# Interface2.net
KiCad netlist of a schematic drawn in Altium Designer
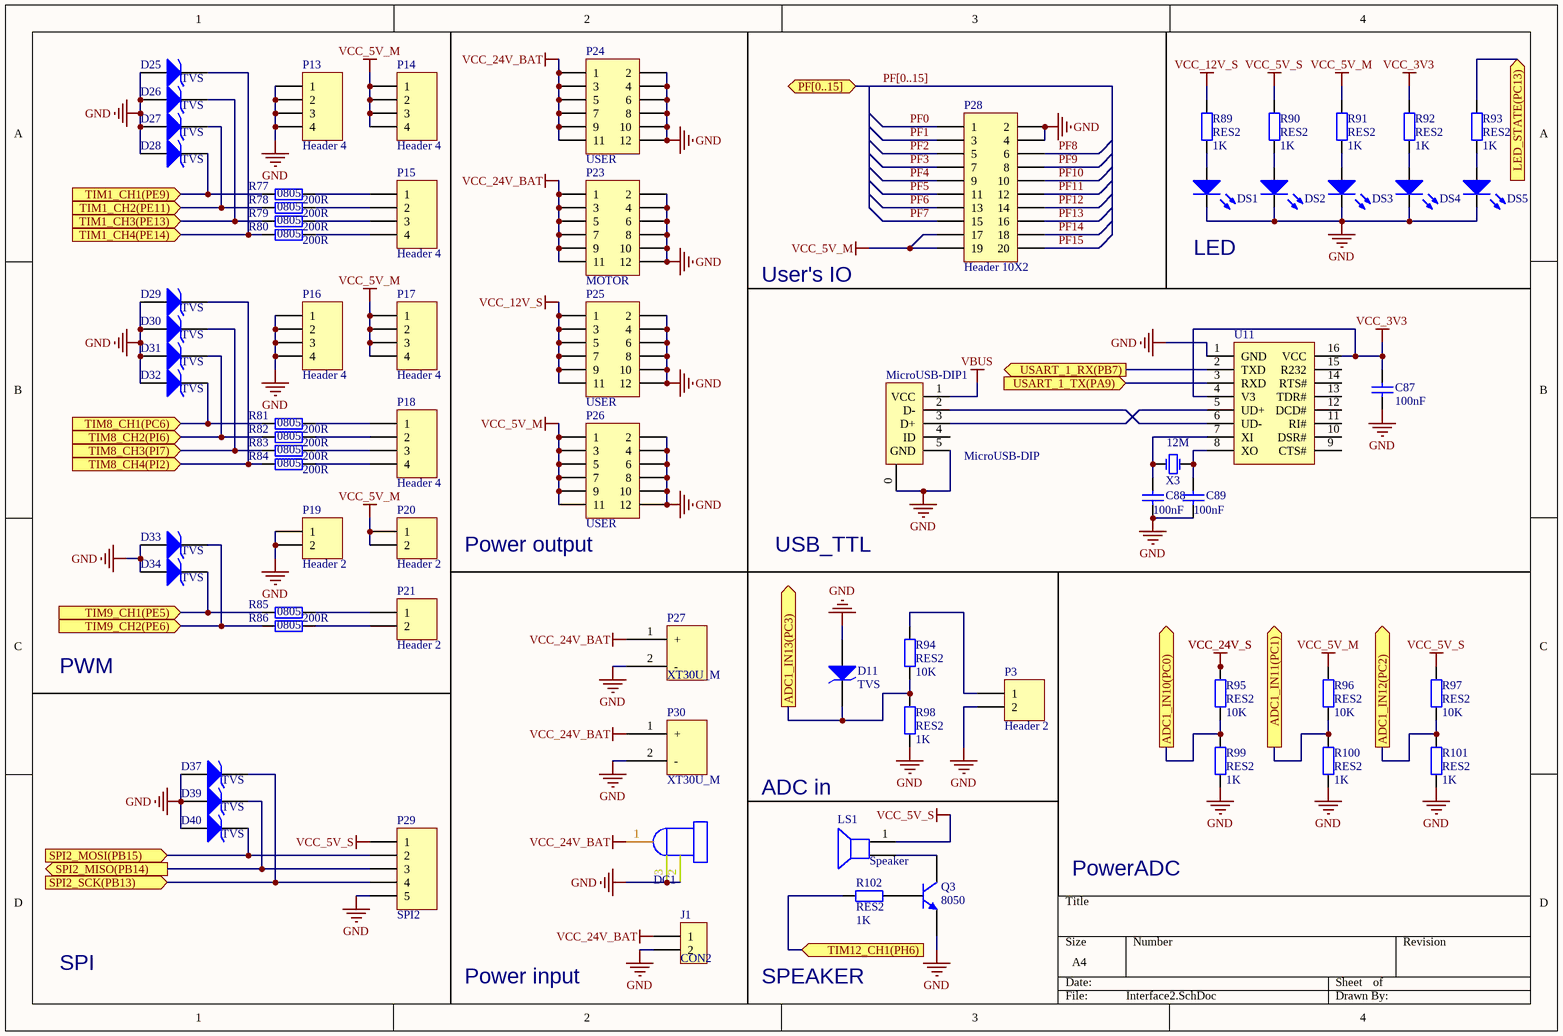
[diagram p0: Interface2.SchDoc]

(export (version "E")
  (design (tool "Eeschema 10.0.6"))
  (components
    (comp (ref "C87")
      (value "100nF")
      (footprint "C 0805_L")
      (fields (field (name "Comment") "CAP"))
      (libsource (lib "QT") (part "CAP"))
    )
    (comp (ref "C88")
      (value "100nF")
      (footprint "C 0805_L")
      (fields (field (name "Comment") "CAP"))
      (libsource (lib "QT") (part "CAP"))
    )
    (comp (ref "C89")
      (value "100nF")
      (footprint "C 0805_L")
      (fields (field (name "Comment") "CAP"))
      (libsource (lib "QT") (part "CAP"))
    )
    (comp (ref "D11")
      (value "TVS")
      (footprint "SOD-523")
      (description "High Conductance Fast Diode")
      (fields (field (name "PUBLISHER") "Altium Limited"))
      (libsource (lib "QT") (part "D"))
    )
    (comp (ref "D25")
      (value "TVS")
      (footprint "SOD-523")
      (description "High Conductance Fast Diode")
      (fields (field (name "PUBLISHER") "Altium Limited"))
      (libsource (lib "QT") (part "D"))
    )
    (comp (ref "D26")
      (value "TVS")
      (footprint "SOD-523")
      (description "High Conductance Fast Diode")
      (fields (field (name "PUBLISHER") "Altium Limited"))
      (libsource (lib "QT") (part "D"))
    )
    (comp (ref "D27")
      (value "TVS")
      (footprint "SOD-523")
      (description "High Conductance Fast Diode")
      (fields (field (name "PUBLISHER") "Altium Limited"))
      (libsource (lib "QT") (part "D"))
    )
    (comp (ref "D28")
      (value "TVS")
      (footprint "SOD-523")
      (description "High Conductance Fast Diode")
      (fields (field (name "PUBLISHER") "Altium Limited"))
      (libsource (lib "QT") (part "D"))
    )
    (comp (ref "D29")
      (value "TVS")
      (footprint "SOD-523")
      (description "High Conductance Fast Diode")
      (fields (field (name "PUBLISHER") "Altium Limited"))
      (libsource (lib "QT") (part "D"))
    )
    (comp (ref "D30")
      (value "TVS")
      (footprint "SOD-523")
      (description "High Conductance Fast Diode")
      (fields (field (name "PUBLISHER") "Altium Limited"))
      (libsource (lib "QT") (part "D"))
    )
    (comp (ref "D31")
      (value "TVS")
      (footprint "SOD-523")
      (description "High Conductance Fast Diode")
      (fields (field (name "PUBLISHER") "Altium Limited"))
      (libsource (lib "QT") (part "D"))
    )
    (comp (ref "D32")
      (value "TVS")
      (footprint "SOD-523")
      (description "High Conductance Fast Diode")
      (fields (field (name "PUBLISHER") "Altium Limited"))
      (libsource (lib "QT") (part "D"))
    )
    (comp (ref "D33")
      (value "TVS")
      (footprint "SOD-523")
      (description "High Conductance Fast Diode")
      (fields (field (name "PUBLISHER") "Altium Limited"))
      (libsource (lib "QT") (part "D"))
    )
    (comp (ref "D34")
      (value "TVS")
      (footprint "SOD-523")
      (description "High Conductance Fast Diode")
      (fields (field (name "PUBLISHER") "Altium Limited"))
      (libsource (lib "QT") (part "D"))
    )
    (comp (ref "D37")
      (value "TVS")
      (footprint "SOD-523")
      (description "High Conductance Fast Diode")
      (fields (field (name "PUBLISHER") "Altium Limited"))
      (libsource (lib "QT") (part "D"))
    )
    (comp (ref "D39")
      (value "TVS")
      (footprint "SOD-523")
      (description "High Conductance Fast Diode")
      (fields (field (name "PUBLISHER") "Altium Limited"))
      (libsource (lib "QT") (part "D"))
    )
    (comp (ref "D40")
      (value "TVS")
      (footprint "SOD-523")
      (description "High Conductance Fast Diode")
      (fields (field (name "PUBLISHER") "Altium Limited"))
      (libsource (lib "QT") (part "D"))
    )
    (comp (ref "DC1") (value "DC") (footprint "DC-005") (libsource (lib "QT") (part "DC")))
    (comp (ref "DS1") (value "LED") (footprint "LED 0805B") (libsource (lib "QT") (part "LED")))
    (comp (ref "DS2") (value "LED") (footprint "LED 0805B") (libsource (lib "QT") (part "LED")))
    (comp (ref "DS3") (value "LED") (footprint "LED 0805B") (libsource (lib "QT") (part "LED")))
    (comp (ref "DS4") (value "LED") (footprint "LED 0805B") (libsource (lib "QT") (part "LED")))
    (comp (ref "DS5") (value "LED") (footprint "LED 0805B") (libsource (lib "QT") (part "LED")))
    (comp (ref "J1") (value "CON2") (footprint "DG1282-5.0") (libsource (lib "常用元件库") (part "CON2")))
    (comp (ref "LS1")
      (value "Speaker")
      (footprint "BEEP 5x9x5.5")
      (description "Loudspeaker")
      (fields (field (name "PUBLISHER") "Altium Limited"))
      (libsource (lib "QT") (part "Speaker"))
    )
    (comp (ref "MicroUSB-DIP1")
      (value "MicroUSB-DIP")
      (footprint "MICRO_USB_DIP")
      (libsource (lib "PineapplePi-F1") (part "MicroUSB-DIP"))
    )
    (comp (ref "P3")
      (value "Header 2")
      (footprint "HDR2.54-LI-2P")
      (description "Header, 2-Pin")
      (fields (field (name "PUBLISHER") "Altium Limited"))
      (libsource (lib "QT") (part "Header 2"))
    )
    (comp (ref "P13")
      (value "Header 4")
      (footprint "HDR2.54-LI-4P")
      (description "Header, 4-Pin")
      (fields (field (name "PUBLISHER") "Altium Limited"))
      (libsource (lib "QT") (part "Header 4"))
    )
    (comp (ref "P14")
      (value "Header 4")
      (footprint "HDR2.54-LI-4P")
      (description "Header, 4-Pin")
      (fields (field (name "PUBLISHER") "Altium Limited"))
      (libsource (lib "QT") (part "Header 4"))
    )
    (comp (ref "P15")
      (value "Header 4")
      (footprint "HDR2.54-LI-4P")
      (description "Header, 4-Pin")
      (fields (field (name "PUBLISHER") "Altium Limited"))
      (libsource (lib "QT") (part "Header 4"))
    )
    (comp (ref "P16")
      (value "Header 4")
      (footprint "HDR2.54-LI-4P")
      (description "Header, 4-Pin")
      (fields (field (name "PUBLISHER") "Altium Limited"))
      (libsource (lib "QT") (part "Header 4"))
    )
    (comp (ref "P17")
      (value "Header 4")
      (footprint "HDR2.54-LI-4P")
      (description "Header, 4-Pin")
      (fields (field (name "PUBLISHER") "Altium Limited"))
      (libsource (lib "QT") (part "Header 4"))
    )
    (comp (ref "P18")
      (value "Header 4")
      (footprint "HDR2.54-LI-4P")
      (description "Header, 4-Pin")
      (fields (field (name "PUBLISHER") "Altium Limited"))
      (libsource (lib "QT") (part "Header 4"))
    )
    (comp (ref "P19")
      (value "Header 2")
      (footprint "HDR2.54-LI-2P")
      (description "Header, 2-Pin")
      (fields (field (name "PUBLISHER") "Altium Limited"))
      (libsource (lib "QT") (part "Header 2"))
    )
    (comp (ref "P20")
      (value "Header 2")
      (footprint "HDR2.54-LI-2P")
      (description "Header, 2-Pin")
      (fields (field (name "PUBLISHER") "Altium Limited"))
      (libsource (lib "QT") (part "Header 2"))
    )
    (comp (ref "P21")
      (value "Header 2")
      (footprint "HDR2.54-LI-2P")
      (description "Header, 2-Pin")
      (fields (field (name "PUBLISHER") "Altium Limited"))
      (libsource (lib "QT") (part "Header 2"))
    )
    (comp (ref "P23")
      (value "MOTOR")
      (footprint "HDR2.54-LI-2x6P")
      (description "Header, 6-Pin, Dual row")
      (fields (field (name "PUBLISHER") "Altium Limited"))
      (libsource (lib "QT") (part "Header 6X2"))
    )
    (comp (ref "P24")
      (value "USER")
      (footprint "HDR2.54-LI-2x6P")
      (description "Header, 6-Pin, Dual row")
      (fields (field (name "PUBLISHER") "Altium Limited"))
      (libsource (lib "QT") (part "Header 6X2"))
    )
    (comp (ref "P25")
      (value "USER")
      (footprint "HDR2.54-LI-2x6P")
      (description "Header, 6-Pin, Dual row")
      (fields (field (name "PUBLISHER") "Altium Limited"))
      (libsource (lib "QT") (part "Header 6X2"))
    )
    (comp (ref "P26")
      (value "USER")
      (footprint "HDR2.54-LI-2x6P")
      (description "Header, 6-Pin, Dual row")
      (fields (field (name "PUBLISHER") "Altium Limited"))
      (libsource (lib "QT") (part "Header 6X2"))
    )
    (comp (ref "P27") (value "XT30U_M") (footprint "XT30U-M") (libsource (lib "常用元件库") (part "XT30U_M")))
    (comp (ref "P28")
      (value "Header 10X2")
      (footprint "HDR10X2_A1")
      (description "Header, 10-Pin")
      (fields (field (name "PUBLISHER") "Altium Limited"))
      (libsource (lib "Fszhang") (part "Header 10X2"))
    )
    (comp (ref "P29")
      (value "SPI2")
      (footprint "HDR2.54-LI-5P")
      (description "Header, 5-Pin")
      (fields (field (name "PUBLISHER") "Altium Limited"))
      (libsource (lib "QT") (part "Header 5"))
    )
    (comp (ref "P30") (value "XT30U_M") (footprint "XT30U-M") (libsource (lib "常用元件库") (part "XT30U_M")))
    (comp (ref "Q3")
      (value "8050")
      (footprint "SOT23-3L")
      (description "NPN Bipolar Transistor")
      (fields (field (name "PUBLISHER") "Altium Limited"))
      (libsource (lib "QT") (part "NPN  SOT"))
    )
    (comp (ref "R77")
      (value "0805")
      (footprint "R 0805_L")
      (description "Resistor")
      (fields (field (name "ALTIUM_VALUE") "200R") (field (name "PUBLISHER") "Altium Limited"))
      (libsource (lib "QT") (part "RES2"))
    )
    (comp (ref "R78")
      (value "0805")
      (footprint "R 0805_L")
      (description "Resistor")
      (fields (field (name "ALTIUM_VALUE") "200R") (field (name "PUBLISHER") "Altium Limited"))
      (libsource (lib "QT") (part "RES2"))
    )
    (comp (ref "R79")
      (value "0805")
      (footprint "R 0805_L")
      (description "Resistor")
      (fields (field (name "ALTIUM_VALUE") "200R") (field (name "PUBLISHER") "Altium Limited"))
      (libsource (lib "QT") (part "RES2"))
    )
    (comp (ref "R80")
      (value "0805")
      (footprint "R 0805_L")
      (description "Resistor")
      (fields (field (name "ALTIUM_VALUE") "200R") (field (name "PUBLISHER") "Altium Limited"))
      (libsource (lib "QT") (part "RES2"))
    )
    (comp (ref "R81")
      (value "0805")
      (footprint "R 0805_L")
      (description "Resistor")
      (fields (field (name "ALTIUM_VALUE") "200R") (field (name "PUBLISHER") "Altium Limited"))
      (libsource (lib "QT") (part "RES2"))
    )
    (comp (ref "R82")
      (value "0805")
      (footprint "R 0805_L")
      (description "Resistor")
      (fields (field (name "ALTIUM_VALUE") "200R") (field (name "PUBLISHER") "Altium Limited"))
      (libsource (lib "QT") (part "RES2"))
    )
    (comp (ref "R83")
      (value "0805")
      (footprint "R 0805_L")
      (description "Resistor")
      (fields (field (name "ALTIUM_VALUE") "200R") (field (name "PUBLISHER") "Altium Limited"))
      (libsource (lib "QT") (part "RES2"))
    )
    (comp (ref "R84")
      (value "0805")
      (footprint "R 0805_L")
      (description "Resistor")
      (fields (field (name "ALTIUM_VALUE") "200R") (field (name "PUBLISHER") "Altium Limited"))
      (libsource (lib "QT") (part "RES2"))
    )
    (comp (ref "R85")
      (value "0805")
      (footprint "R 0805_L")
      (description "Resistor")
      (fields (field (name "ALTIUM_VALUE") "200R") (field (name "PUBLISHER") "Altium Limited"))
      (libsource (lib "QT") (part "RES2"))
    )
    (comp (ref "R86")
      (value "0805")
      (footprint "R 0805_L")
      (description "Resistor")
      (fields (field (name "PUBLISHER") "Altium Limited"))
      (libsource (lib "QT") (part "RES2"))
    )
    (comp (ref "R89")
      (value "RES2")
      (footprint "R 0805_L")
      (description "Resistor")
      (fields (field (name "ALTIUM_VALUE") "1K") (field (name "PUBLISHER") "Altium Limited"))
      (libsource (lib "") (part "RES2_1"))
    )
    (comp (ref "R90")
      (value "RES2")
      (footprint "R 0805_L")
      (description "Resistor")
      (fields (field (name "ALTIUM_VALUE") "1K") (field (name "PUBLISHER") "Altium Limited"))
      (libsource (lib "") (part "RES2_1"))
    )
    (comp (ref "R91")
      (value "RES2")
      (footprint "R 0805_L")
      (description "Resistor")
      (fields (field (name "ALTIUM_VALUE") "1K") (field (name "PUBLISHER") "Altium Limited"))
      (libsource (lib "") (part "RES2_1"))
    )
    (comp (ref "R92")
      (value "RES2")
      (footprint "R 0805_L")
      (description "Resistor")
      (fields (field (name "ALTIUM_VALUE") "1K") (field (name "PUBLISHER") "Altium Limited"))
      (libsource (lib "") (part "RES2_1"))
    )
    (comp (ref "R93")
      (value "RES2")
      (footprint "R 0805_L")
      (description "Resistor")
      (fields (field (name "ALTIUM_VALUE") "1K") (field (name "PUBLISHER") "Altium Limited"))
      (libsource (lib "") (part "RES2_1"))
    )
    (comp (ref "R94")
      (value "RES2")
      (footprint "R 0805_L")
      (description "Resistor")
      (fields (field (name "ALTIUM_VALUE") "10K") (field (name "PUBLISHER") "Altium Limited"))
      (libsource (lib "") (part "RES2_1"))
    )
    (comp (ref "R95")
      (value "RES2")
      (footprint "R 0805_L")
      (description "Resistor")
      (fields (field (name "ALTIUM_VALUE") "10K") (field (name "PUBLISHER") "Altium Limited"))
      (libsource (lib "") (part "RES2_1"))
    )
    (comp (ref "R96")
      (value "RES2")
      (footprint "R 0805_L")
      (description "Resistor")
      (fields (field (name "ALTIUM_VALUE") "10K") (field (name "PUBLISHER") "Altium Limited"))
      (libsource (lib "") (part "RES2_1"))
    )
    (comp (ref "R97")
      (value "RES2")
      (footprint "R 0805_L")
      (description "Resistor")
      (fields (field (name "ALTIUM_VALUE") "10K") (field (name "PUBLISHER") "Altium Limited"))
      (libsource (lib "") (part "RES2_1"))
    )
    (comp (ref "R98")
      (value "RES2")
      (footprint "R 0805_L")
      (description "Resistor")
      (fields (field (name "ALTIUM_VALUE") "1K") (field (name "PUBLISHER") "Altium Limited"))
      (libsource (lib "") (part "RES2_1"))
    )
    (comp (ref "R99")
      (value "RES2")
      (footprint "R 0805_L")
      (description "Resistor")
      (fields (field (name "ALTIUM_VALUE") "1K") (field (name "PUBLISHER") "Altium Limited"))
      (libsource (lib "") (part "RES2_1"))
    )
    (comp (ref "R100")
      (value "RES2")
      (footprint "R 0805_L")
      (description "Resistor")
      (fields (field (name "ALTIUM_VALUE") "1K") (field (name "PUBLISHER") "Altium Limited"))
      (libsource (lib "") (part "RES2_1"))
    )
    (comp (ref "R101")
      (value "RES2")
      (footprint "R 0805_L")
      (description "Resistor")
      (fields (field (name "ALTIUM_VALUE") "1K") (field (name "PUBLISHER") "Altium Limited"))
      (libsource (lib "") (part "RES2_1"))
    )
    (comp (ref "R102")
      (value "RES2")
      (footprint "R 0805_L")
      (description "Resistor")
      (fields (field (name "ALTIUM_VALUE") "1K") (field (name "PUBLISHER") "Altium Limited"))
      (libsource (lib "") (part "RES2_2"))
    )
    (comp (ref "U11") (value "CH340G") (footprint "SOP16_M") (libsource (lib "史福祥库") (part "CH340G")))
    (comp (ref "X3") (value "12M") (footprint "OSC HC-49S") (libsource (lib "QT") (part "YX")))
  )
  (nets
    (net (code "1") (name "/ADC1_IN10(PC0)") (class "Default")
      (node (ref "R95") (pin "1") (pinfunction "1_1") (pintype "passive"))
      (node (ref "R99") (pin "2") (pinfunction "2_2") (pintype "passive"))
    )
    (net (code "2") (name "/ADC1_IN11(PC1)") (class "Default")
      (node (ref "R100") (pin "2") (pinfunction "2_2") (pintype "passive"))
      (node (ref "R96") (pin "1") (pinfunction "1_1") (pintype "passive"))
    )
    (net (code "3") (name "/ADC1_IN12(PC2)") (class "Default")
      (node (ref "R101") (pin "2") (pinfunction "2_2") (pintype "passive"))
      (node (ref "R97") (pin "1") (pinfunction "1_1") (pintype "passive"))
    )
    (net (code "4") (name "/ADC1_IN13(PC3)") (class "Default")
      (node (ref "D11") (pin "2") (pinfunction "K_2") (pintype "passive"))
      (node (ref "R94") (pin "1") (pinfunction "1_1") (pintype "passive"))
      (node (ref "R98") (pin "2") (pinfunction "2_2") (pintype "passive"))
    )
    (net (code "5") (name "/LED_STATE(PC13)") (class "Default")
      (node (ref "R93") (pin "2") (pinfunction "2_2") (pintype "passive"))
    )
    (net (code "6") (name "/PF0") (class "Default")
      (node (ref "P28") (pin "1") (pinfunction "1_1") (pintype "passive"))
    )
    (net (code "7") (name "/PF1") (class "Default")
      (node (ref "P28") (pin "3") (pinfunction "3_3") (pintype "passive"))
    )
    (net (code "8") (name "/PF2") (class "Default")
      (node (ref "P28") (pin "5") (pinfunction "5_5") (pintype "passive"))
    )
    (net (code "9") (name "/PF3") (class "Default")
      (node (ref "P28") (pin "7") (pinfunction "7_7") (pintype "passive"))
    )
    (net (code "10") (name "/PF4") (class "Default")
      (node (ref "P28") (pin "9") (pinfunction "9_9") (pintype "passive"))
    )
    (net (code "11") (name "/PF5") (class "Default")
      (node (ref "P28") (pin "11") (pinfunction "11_11") (pintype "passive"))
    )
    (net (code "12") (name "/PF6") (class "Default")
      (node (ref "P28") (pin "13") (pinfunction "13_13") (pintype "passive"))
    )
    (net (code "13") (name "/PF7") (class "Default")
      (node (ref "P28") (pin "15") (pinfunction "15_15") (pintype "passive"))
    )
    (net (code "14") (name "/PF8") (class "Default")
      (node (ref "P28") (pin "6") (pinfunction "6_6") (pintype "passive"))
    )
    (net (code "15") (name "/PF9") (class "Default")
      (node (ref "P28") (pin "8") (pinfunction "8_8") (pintype "passive"))
    )
    (net (code "16") (name "/PF10") (class "Default")
      (node (ref "P28") (pin "10") (pinfunction "10_10") (pintype "passive"))
    )
    (net (code "17") (name "/PF11") (class "Default")
      (node (ref "P28") (pin "12") (pinfunction "12_12") (pintype "passive"))
    )
    (net (code "18") (name "/PF12") (class "Default")
      (node (ref "P28") (pin "14") (pinfunction "14_14") (pintype "passive"))
    )
    (net (code "19") (name "/PF13") (class "Default")
      (node (ref "P28") (pin "16") (pinfunction "16_16") (pintype "passive"))
    )
    (net (code "20") (name "/PF14") (class "Default")
      (node (ref "P28") (pin "18") (pinfunction "18_18") (pintype "passive"))
    )
    (net (code "21") (name "/PF15") (class "Default")
      (node (ref "P28") (pin "20") (pinfunction "20_20") (pintype "passive"))
    )
    (net (code "23") (name "/SPI2_MISO(PB14)") (class "Default")
      (node (ref "D39") (pin "2") (pinfunction "K_2") (pintype "passive"))
      (node (ref "P29") (pin "3") (pinfunction "3_3") (pintype "passive"))
    )
    (net (code "24") (name "/SPI2_MOSI(PB15)") (class "Default")
      (node (ref "D40") (pin "2") (pinfunction "K_2") (pintype "passive"))
      (node (ref "P29") (pin "2") (pinfunction "2_2") (pintype "passive"))
    )
    (net (code "25") (name "/SPI2_SCK(PB13)") (class "Default")
      (node (ref "D37") (pin "2") (pinfunction "K_2") (pintype "passive"))
      (node (ref "P29") (pin "4") (pinfunction "4_4") (pintype "passive"))
    )
    (net (code "26") (name "/TIM1_CH1(PE9)") (class "Default")
      (node (ref "D28") (pin "2") (pinfunction "K_2") (pintype "passive"))
      (node (ref "R77") (pin "1") (pinfunction "1_1") (pintype "passive"))
    )
    (net (code "27") (name "/TIM1_CH2(PE11)") (class "Default")
      (node (ref "D27") (pin "2") (pinfunction "K_2") (pintype "passive"))
      (node (ref "R78") (pin "1") (pinfunction "1_1") (pintype "passive"))
    )
    (net (code "28") (name "/TIM1_CH3(PE13)") (class "Default")
      (node (ref "D26") (pin "2") (pinfunction "K_2") (pintype "passive"))
      (node (ref "R79") (pin "1") (pinfunction "1_1") (pintype "passive"))
    )
    (net (code "29") (name "/TIM1_CH4(PE14)") (class "Default")
      (node (ref "D25") (pin "2") (pinfunction "K_2") (pintype "passive"))
      (node (ref "R80") (pin "1") (pinfunction "1_1") (pintype "passive"))
    )
    (net (code "30") (name "/TIM8_CH1(PC6)") (class "Default")
      (node (ref "D32") (pin "2") (pinfunction "K_2") (pintype "passive"))
      (node (ref "R81") (pin "1") (pinfunction "1_1") (pintype "passive"))
    )
    (net (code "31") (name "/TIM8_CH2(PI6)") (class "Default")
      (node (ref "D31") (pin "2") (pinfunction "K_2") (pintype "passive"))
      (node (ref "R82") (pin "1") (pinfunction "1_1") (pintype "passive"))
    )
    (net (code "32") (name "/TIM8_CH3(PI7)") (class "Default")
      (node (ref "D30") (pin "2") (pinfunction "K_2") (pintype "passive"))
      (node (ref "R83") (pin "1") (pinfunction "1_1") (pintype "passive"))
    )
    (net (code "33") (name "/TIM8_CH4(PI2)") (class "Default")
      (node (ref "D29") (pin "2") (pinfunction "K_2") (pintype "passive"))
      (node (ref "R84") (pin "1") (pinfunction "1_1") (pintype "passive"))
    )
    (net (code "34") (name "/TIM9_CH1(PE5)") (class "Default")
      (node (ref "D34") (pin "2") (pinfunction "K_2") (pintype "passive"))
      (node (ref "R85") (pin "1") (pinfunction "1_1") (pintype "passive"))
    )
    (net (code "35") (name "/TIM9_CH2(PE6)") (class "Default")
      (node (ref "D33") (pin "2") (pinfunction "K_2") (pintype "passive"))
      (node (ref "R86") (pin "1") (pinfunction "1_1") (pintype "passive"))
    )
    (net (code "36") (name "/TIM12_CH1(PH6)") (class "Default")
      (node (ref "R102") (pin "2") (pinfunction "2_2") (pintype "passive"))
    )
    (net (code "37") (name "/USART_1_RX(PB7)") (class "Default")
      (node (ref "U11") (pin "2") (pinfunction "TXD_2") (pintype "passive"))
    )
    (net (code "38") (name "/USART_1_TX(PA9)") (class "Default")
      (node (ref "U11") (pin "3") (pinfunction "RXD_3") (pintype "passive"))
    )
    (net (code "39") (name "GND") (class "Default")
      (node (ref "C87") (pin "1") (pinfunction "1_1") (pintype "passive"))
      (node (ref "C88") (pin "1") (pinfunction "1_1") (pintype "passive"))
      (node (ref "C89") (pin "1") (pinfunction "1_1") (pintype "passive"))
      (node (ref "D11") (pin "1") (pinfunction "A_1") (pintype "passive"))
      (node (ref "D25") (pin "1") (pinfunction "A_1") (pintype "passive"))
      (node (ref "D26") (pin "1") (pinfunction "A_1") (pintype "passive"))
      (node (ref "D27") (pin "1") (pinfunction "A_1") (pintype "passive"))
      (node (ref "D28") (pin "1") (pinfunction "A_1") (pintype "passive"))
      (node (ref "D29") (pin "1") (pinfunction "A_1") (pintype "passive"))
      (node (ref "D30") (pin "1") (pinfunction "A_1") (pintype "passive"))
      (node (ref "D31") (pin "1") (pinfunction "A_1") (pintype "passive"))
      (node (ref "D32") (pin "1") (pinfunction "A_1") (pintype "passive"))
      (node (ref "D33") (pin "1") (pinfunction "A_1") (pintype "passive"))
      (node (ref "D34") (pin "1") (pinfunction "A_1") (pintype "passive"))
      (node (ref "D37") (pin "1") (pinfunction "A_1") (pintype "passive"))
      (node (ref "D39") (pin "1") (pinfunction "A_1") (pintype "passive"))
      (node (ref "D40") (pin "1") (pinfunction "A_1") (pintype "passive"))
      (node (ref "DC1") (pin "2") (pinfunction "-_2") (pintype "passive"))
      (node (ref "DC1") (pin "3") (pinfunction "-_3") (pintype "passive"))
      (node (ref "DS1") (pin "2") (pinfunction "K_2") (pintype "passive"))
      (node (ref "DS2") (pin "2") (pinfunction "K_2") (pintype "passive"))
      (node (ref "DS3") (pin "2") (pinfunction "K_2") (pintype "passive"))
      (node (ref "DS4") (pin "2") (pinfunction "K_2") (pintype "passive"))
      (node (ref "DS5") (pin "2") (pinfunction "K_2") (pintype "passive"))
      (node (ref "J1") (pin "2") (pinfunction "2_2") (pintype "passive"))
      (node (ref "MicroUSB-DIP1") (pin "0") (pintype "passive"))
      (node (ref "MicroUSB-DIP1") (pin "5") (pinfunction "GND_5") (pintype "power_in"))
      (node (ref "P13") (pin "1") (pinfunction "1_1") (pintype "passive"))
      (node (ref "P13") (pin "2") (pinfunction "2_2") (pintype "passive"))
      (node (ref "P13") (pin "3") (pinfunction "3_3") (pintype "passive"))
      (node (ref "P13") (pin "4") (pinfunction "4_4") (pintype "passive"))
      (node (ref "P16") (pin "1") (pinfunction "1_1") (pintype "passive"))
      (node (ref "P16") (pin "2") (pinfunction "2_2") (pintype "passive"))
      (node (ref "P16") (pin "3") (pinfunction "3_3") (pintype "passive"))
      (node (ref "P16") (pin "4") (pinfunction "4_4") (pintype "passive"))
      (node (ref "P19") (pin "1") (pinfunction "1_1") (pintype "passive"))
      (node (ref "P19") (pin "2") (pinfunction "2_2") (pintype "passive"))
      (node (ref "P23") (pin "10") (pinfunction "10_10") (pintype "passive"))
      (node (ref "P23") (pin "12") (pinfunction "12_12") (pintype "passive"))
      (node (ref "P23") (pin "2") (pinfunction "2_2") (pintype "passive"))
      (node (ref "P23") (pin "4") (pinfunction "4_4") (pintype "passive"))
      (node (ref "P23") (pin "6") (pinfunction "6_6") (pintype "passive"))
      (node (ref "P23") (pin "8") (pinfunction "8_8") (pintype "passive"))
      (node (ref "P24") (pin "10") (pinfunction "10_10") (pintype "passive"))
      (node (ref "P24") (pin "12") (pinfunction "12_12") (pintype "passive"))
      (node (ref "P24") (pin "2") (pinfunction "2_2") (pintype "passive"))
      (node (ref "P24") (pin "4") (pinfunction "4_4") (pintype "passive"))
      (node (ref "P24") (pin "6") (pinfunction "6_6") (pintype "passive"))
      (node (ref "P24") (pin "8") (pinfunction "8_8") (pintype "passive"))
      (node (ref "P25") (pin "10") (pinfunction "10_10") (pintype "passive"))
      (node (ref "P25") (pin "12") (pinfunction "12_12") (pintype "passive"))
      (node (ref "P25") (pin "2") (pinfunction "2_2") (pintype "passive"))
      (node (ref "P25") (pin "4") (pinfunction "4_4") (pintype "passive"))
      (node (ref "P25") (pin "6") (pinfunction "6_6") (pintype "passive"))
      (node (ref "P25") (pin "8") (pinfunction "8_8") (pintype "passive"))
      (node (ref "P26") (pin "10") (pinfunction "10_10") (pintype "passive"))
      (node (ref "P26") (pin "12") (pinfunction "12_12") (pintype "passive"))
      (node (ref "P26") (pin "2") (pinfunction "2_2") (pintype "passive"))
      (node (ref "P26") (pin "4") (pinfunction "4_4") (pintype "passive"))
      (node (ref "P26") (pin "6") (pinfunction "6_6") (pintype "passive"))
      (node (ref "P26") (pin "8") (pinfunction "8_8") (pintype "passive"))
      (node (ref "P27") (pin "2") (pinfunction "-_2") (pintype "passive"))
      (node (ref "P28") (pin "2") (pinfunction "2_2") (pintype "passive"))
      (node (ref "P28") (pin "4") (pinfunction "4_4") (pintype "passive"))
      (node (ref "P29") (pin "5") (pinfunction "5_5") (pintype "passive"))
      (node (ref "P3") (pin "2") (pinfunction "2_2") (pintype "passive"))
      (node (ref "P30") (pin "2") (pinfunction "-_2") (pintype "passive"))
      (node (ref "Q3") (pin "2") (pinfunction "E_2") (pintype "passive"))
      (node (ref "R100") (pin "1") (pinfunction "1_1") (pintype "passive"))
      (node (ref "R101") (pin "1") (pinfunction "1_1") (pintype "passive"))
      (node (ref "R98") (pin "1") (pinfunction "1_1") (pintype "passive"))
      (node (ref "R99") (pin "1") (pinfunction "1_1") (pintype "passive"))
      (node (ref "U11") (pin "1") (pinfunction "GND_1") (pintype "passive"))
    )
    (net (code "40") (name "Net-(DS1-A)") (class "Default")
      (node (ref "DS1") (pin "1") (pinfunction "A_1") (pintype "passive"))
      (node (ref "R89") (pin "1") (pinfunction "1_1") (pintype "passive"))
    )
    (net (code "41") (name "Net-(DS2-A)") (class "Default")
      (node (ref "DS2") (pin "1") (pinfunction "A_1") (pintype "passive"))
      (node (ref "R90") (pin "1") (pinfunction "1_1") (pintype "passive"))
    )
    (net (code "42") (name "Net-(DS3-A)") (class "Default")
      (node (ref "DS3") (pin "1") (pinfunction "A_1") (pintype "passive"))
      (node (ref "R91") (pin "1") (pinfunction "1_1") (pintype "passive"))
    )
    (net (code "43") (name "Net-(DS4-A)") (class "Default")
      (node (ref "DS4") (pin "1") (pinfunction "A_1") (pintype "passive"))
      (node (ref "R92") (pin "1") (pinfunction "1_1") (pintype "passive"))
    )
    (net (code "44") (name "Net-(DS5-A)") (class "Default")
      (node (ref "DS5") (pin "1") (pinfunction "A_1") (pintype "passive"))
      (node (ref "R93") (pin "1") (pinfunction "1_1") (pintype "passive"))
    )
    (net (code "45") (name "Net-(MicroUSB-DIP1-D+)") (class "Default")
      (node (ref "MicroUSB-DIP1") (pin "3") (pinfunction "D+_3") (pintype "power_in"))
      (node (ref "U11") (pin "5") (pinfunction "UD+_5") (pintype "passive"))
    )
    (net (code "46") (name "Net-(MicroUSB-DIP1-D-)") (class "Default")
      (node (ref "MicroUSB-DIP1") (pin "2") (pinfunction "D-_2") (pintype "power_in"))
      (node (ref "U11") (pin "6") (pinfunction "UD-_6") (pintype "passive"))
    )
    (net (code "47") (name "Net-(P3-Pad1)") (class "Default")
      (node (ref "P3") (pin "1") (pinfunction "1_1") (pintype "passive"))
      (node (ref "R94") (pin "2") (pinfunction "2_2") (pintype "passive"))
    )
    (net (code "48") (name "Net-(P15-Pad1)") (class "Default")
      (node (ref "P15") (pin "1") (pinfunction "1_1") (pintype "passive"))
      (node (ref "R77") (pin "2") (pinfunction "2_2") (pintype "passive"))
    )
    (net (code "49") (name "Net-(P15-Pad2)") (class "Default")
      (node (ref "P15") (pin "2") (pinfunction "2_2") (pintype "passive"))
      (node (ref "R78") (pin "2") (pinfunction "2_2") (pintype "passive"))
    )
    (net (code "50") (name "Net-(P15-Pad3)") (class "Default")
      (node (ref "P15") (pin "3") (pinfunction "3_3") (pintype "passive"))
      (node (ref "R79") (pin "2") (pinfunction "2_2") (pintype "passive"))
    )
    (net (code "51") (name "Net-(P15-Pad4)") (class "Default")
      (node (ref "P15") (pin "4") (pinfunction "4_4") (pintype "passive"))
      (node (ref "R80") (pin "2") (pinfunction "2_2") (pintype "passive"))
    )
    (net (code "52") (name "Net-(P18-Pad1)") (class "Default")
      (node (ref "P18") (pin "1") (pinfunction "1_1") (pintype "passive"))
      (node (ref "R81") (pin "2") (pinfunction "2_2") (pintype "passive"))
    )
    (net (code "53") (name "Net-(P18-Pad2)") (class "Default")
      (node (ref "P18") (pin "2") (pinfunction "2_2") (pintype "passive"))
      (node (ref "R82") (pin "2") (pinfunction "2_2") (pintype "passive"))
    )
    (net (code "54") (name "Net-(P18-Pad3)") (class "Default")
      (node (ref "P18") (pin "3") (pinfunction "3_3") (pintype "passive"))
      (node (ref "R83") (pin "2") (pinfunction "2_2") (pintype "passive"))
    )
    (net (code "55") (name "Net-(P18-Pad4)") (class "Default")
      (node (ref "P18") (pin "4") (pinfunction "4_4") (pintype "passive"))
      (node (ref "R84") (pin "2") (pinfunction "2_2") (pintype "passive"))
    )
    (net (code "56") (name "Net-(P21-Pad1)") (class "Default")
      (node (ref "P21") (pin "1") (pinfunction "1_1") (pintype "passive"))
      (node (ref "R85") (pin "2") (pinfunction "2_2") (pintype "passive"))
    )
    (net (code "57") (name "Net-(P21-Pad2)") (class "Default")
      (node (ref "P21") (pin "2") (pinfunction "2_2") (pintype "passive"))
      (node (ref "R86") (pin "2") (pinfunction "2_2") (pintype "passive"))
    )
    (net (code "58") (name "Net-(Q3-B)") (class "Default")
      (node (ref "Q3") (pin "1") (pinfunction "B_1") (pintype "passive"))
      (node (ref "R102") (pin "1") (pinfunction "1_1") (pintype "passive"))
    )
    (net (code "59") (name "Net-(Q3-C)") (class "Default")
      (node (ref "LS1") (pin "2") (pinfunction "2_2") (pintype "passive"))
      (node (ref "Q3") (pin "3") (pinfunction "C_3") (pintype "passive"))
    )
    (net (code "60") (name "Net-(U11-XI)") (class "Default")
      (node (ref "C88") (pin "2") (pinfunction "2_2") (pintype "passive"))
      (node (ref "U11") (pin "7") (pinfunction "XI_7") (pintype "passive"))
      (node (ref "X3") (pin "1") (pinfunction "OSC1_1") (pintype "passive"))
    )
    (net (code "61") (name "Net-(U11-XO)") (class "Default")
      (node (ref "C89") (pin "2") (pinfunction "2_2") (pintype "passive"))
      (node (ref "U11") (pin "8") (pinfunction "XO_8") (pintype "passive"))
      (node (ref "X3") (pin "2") (pinfunction "OSC2_2") (pintype "passive"))
    )
    (net (code "62") (name "VBUS") (class "Default")
      (node (ref "MicroUSB-DIP1") (pin "1") (pinfunction "VCC_1") (pintype "power_in"))
    )
    (net (code "63") (name "VCC_3V3") (class "Default")
      (node (ref "C87") (pin "2") (pinfunction "2_2") (pintype "passive"))
      (node (ref "R92") (pin "2") (pinfunction "2_2") (pintype "passive"))
      (node (ref "U11") (pin "16") (pinfunction "VCC_16") (pintype "passive"))
      (node (ref "U11") (pin "4") (pinfunction "V3_4") (pintype "passive"))
    )
    (net (code "64") (name "VCC_5V_M") (class "Default")
      (node (ref "P14") (pin "1") (pinfunction "1_1") (pintype "passive"))
      (node (ref "P14") (pin "2") (pinfunction "2_2") (pintype "passive"))
      (node (ref "P14") (pin "3") (pinfunction "3_3") (pintype "passive"))
      (node (ref "P14") (pin "4") (pinfunction "4_4") (pintype "passive"))
      (node (ref "P17") (pin "1") (pinfunction "1_1") (pintype "passive"))
      (node (ref "P17") (pin "2") (pinfunction "2_2") (pintype "passive"))
      (node (ref "P17") (pin "3") (pinfunction "3_3") (pintype "passive"))
      (node (ref "P17") (pin "4") (pinfunction "4_4") (pintype "passive"))
      (node (ref "P20") (pin "1") (pinfunction "1_1") (pintype "passive"))
      (node (ref "P20") (pin "2") (pinfunction "2_2") (pintype "passive"))
      (node (ref "P26") (pin "1") (pinfunction "1_1") (pintype "passive"))
      (node (ref "P26") (pin "11") (pinfunction "11_11") (pintype "passive"))
      (node (ref "P26") (pin "3") (pinfunction "3_3") (pintype "passive"))
      (node (ref "P26") (pin "5") (pinfunction "5_5") (pintype "passive"))
      (node (ref "P26") (pin "7") (pinfunction "7_7") (pintype "passive"))
      (node (ref "P26") (pin "9") (pinfunction "9_9") (pintype "passive"))
      (node (ref "P28") (pin "17") (pinfunction "17_17") (pintype "passive"))
      (node (ref "P28") (pin "19") (pinfunction "19_19") (pintype "passive"))
      (node (ref "R91") (pin "2") (pinfunction "2_2") (pintype "passive"))
      (node (ref "R96") (pin "2") (pinfunction "2_2") (pintype "passive"))
    )
    (net (code "65") (name "VCC_5V_S") (class "Default")
      (node (ref "LS1") (pin "1") (pinfunction "1_1") (pintype "passive"))
      (node (ref "P29") (pin "1") (pinfunction "1_1") (pintype "passive"))
      (node (ref "R90") (pin "2") (pinfunction "2_2") (pintype "passive"))
      (node (ref "R97") (pin "2") (pinfunction "2_2") (pintype "passive"))
    )
    (net (code "66") (name "VCC_12V_S") (class "Default")
      (node (ref "P25") (pin "1") (pinfunction "1_1") (pintype "passive"))
      (node (ref "P25") (pin "11") (pinfunction "11_11") (pintype "passive"))
      (node (ref "P25") (pin "3") (pinfunction "3_3") (pintype "passive"))
      (node (ref "P25") (pin "5") (pinfunction "5_5") (pintype "passive"))
      (node (ref "P25") (pin "7") (pinfunction "7_7") (pintype "passive"))
      (node (ref "P25") (pin "9") (pinfunction "9_9") (pintype "passive"))
      (node (ref "R89") (pin "2") (pinfunction "2_2") (pintype "passive"))
    )
    (net (code "67") (name "VCC_24V_BAT") (class "Default")
      (node (ref "DC1") (pin "1") (pinfunction "+_1") (pintype "passive"))
      (node (ref "J1") (pin "1") (pinfunction "1_1") (pintype "passive"))
      (node (ref "P23") (pin "1") (pinfunction "1_1") (pintype "passive"))
      (node (ref "P23") (pin "11") (pinfunction "11_11") (pintype "passive"))
      (node (ref "P23") (pin "3") (pinfunction "3_3") (pintype "passive"))
      (node (ref "P23") (pin "5") (pinfunction "5_5") (pintype "passive"))
      (node (ref "P23") (pin "7") (pinfunction "7_7") (pintype "passive"))
      (node (ref "P23") (pin "9") (pinfunction "9_9") (pintype "passive"))
      (node (ref "P24") (pin "1") (pinfunction "1_1") (pintype "passive"))
      (node (ref "P24") (pin "11") (pinfunction "11_11") (pintype "passive"))
      (node (ref "P24") (pin "3") (pinfunction "3_3") (pintype "passive"))
      (node (ref "P24") (pin "5") (pinfunction "5_5") (pintype "passive"))
      (node (ref "P24") (pin "7") (pinfunction "7_7") (pintype "passive"))
      (node (ref "P24") (pin "9") (pinfunction "9_9") (pintype "passive"))
      (node (ref "P27") (pin "1") (pinfunction "+_1") (pintype "passive"))
      (node (ref "P30") (pin "1") (pinfunction "+_1") (pintype "passive"))
    )
    (net (code "68") (name "VCC_24V_S") (class "Default")
      (node (ref "R95") (pin "2") (pinfunction "2_2") (pintype "passive"))
    )
    (net (code "69") (name "unconnected-(MicroUSB-DIP1-ID-Pad4)") (class "Default")
      (node (ref "MicroUSB-DIP1") (pin "4") (pinfunction "ID_4") (pintype "passive"))
    )
    (net (code "70") (name "unconnected-(U11-CTS#-Pad9)") (class "Default")
      (node (ref "U11") (pin "9") (pinfunction "CTS#_9") (pintype "passive"))
    )
    (net (code "71") (name "unconnected-(U11-DCD#-Pad12)") (class "Default")
      (node (ref "U11") (pin "12") (pinfunction "DCD#_12") (pintype "passive"))
    )
    (net (code "72") (name "unconnected-(U11-DSR#-Pad10)") (class "Default")
      (node (ref "U11") (pin "10") (pinfunction "DSR#_10") (pintype "passive"))
    )
    (net (code "73") (name "unconnected-(U11-R232-Pad15)") (class "Default")
      (node (ref "U11") (pin "15") (pinfunction "R232_15") (pintype "passive"))
    )
    (net (code "74") (name "unconnected-(U11-RI#-Pad11)") (class "Default")
      (node (ref "U11") (pin "11") (pinfunction "RI#_11") (pintype "passive"))
    )
    (net (code "75") (name "unconnected-(U11-RTS#-Pad14)") (class "Default")
      (node (ref "U11") (pin "14") (pinfunction "RTS#_14") (pintype "passive"))
    )
    (net (code "76") (name "unconnected-(U11-TDR#-Pad13)") (class "Default")
      (node (ref "U11") (pin "13") (pinfunction "TDR#_13") (pintype "passive"))
    )
  )
)
